# 11_power_input_and_regualtors.net
KiCad netlist of a schematic drawn in Altium Designer
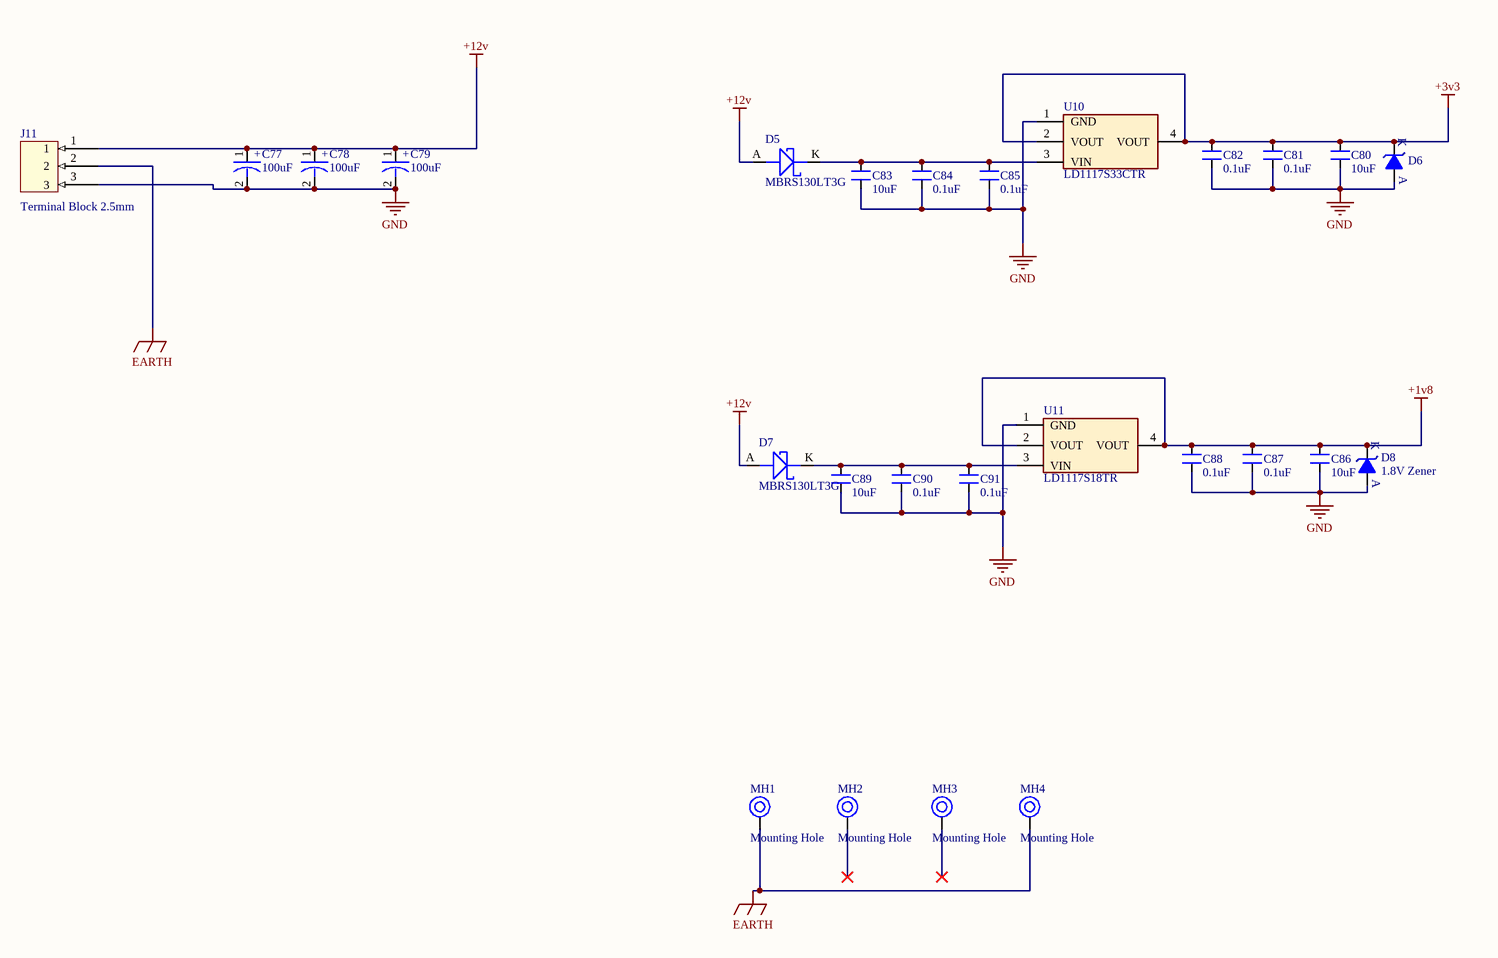
[diagram p0: [11]power_input_and_regualtors.SchDoc]

(export (version "E")
  (design (tool "Eeschema 10.0.6"))
  (components
    (comp (ref "C77")
      (value "100uF")
      (footprint "ACAP_P305_D393_H393_RAD")
      (description "100µF 50V Aluminum Polymer Capacitor Radial, Can - SMD 28mOhm 4000 Hrs @ 125°C")
      (fields
        (field (name "MANUFACTURER") "Nichicon")
        (field (name "MANUFACTURER PART NUMBER") "GYA1H101MCQ1GS")
      )
      (libsource (lib "ESTEEMPCBLIB") (part "CAP-P_100uF-50V-20%-RAD"))
    )
    (comp (ref "C78")
      (value "100uF")
      (footprint "ACAP_P305_D393_H393_RAD")
      (description "100µF 50V Aluminum Polymer Capacitor Radial, Can - SMD 28mOhm 4000 Hrs @ 125°C")
      (fields
        (field (name "MANUFACTURER") "Nichicon")
        (field (name "MANUFACTURER PART NUMBER") "GYA1H101MCQ1GS")
      )
      (libsource (lib "ESTEEMPCBLIB") (part "CAP-P_100uF-50V-20%-RAD"))
    )
    (comp (ref "C79")
      (value "100uF")
      (footprint "ACAP_P305_D393_H393_RAD")
      (description "100µF 50V Aluminum Polymer Capacitor Radial, Can - SMD 28mOhm 4000 Hrs @ 125°C")
      (fields
        (field (name "MANUFACTURER") "Nichicon")
        (field (name "MANUFACTURER PART NUMBER") "GYA1H101MCQ1GS")
      )
      (libsource (lib "ESTEEMPCBLIB") (part "CAP-P_100uF-50V-20%-RAD"))
    )
    (comp (ref "C80")
      (value "10uF")
      (footprint "CAP_1206")
      (description "10µF ±10% 50V Ceramic Capacitor X7R 1206 (3216 Metric)")
      (fields
        (field (name "MANUFACTURER") "KEMET")
        (field (name "MANUFACTURER PART NUMBER") "CL31B106KBHNNNE")
      )
      (libsource (lib "ESTEEMPCBLIB") (part "CAP_10uF-50V-10%-1206"))
    )
    (comp (ref "C81")
      (value "0.1uF")
      (footprint "CAP_0805")
      (description "0.1µF ±5% 50V Ceramic Capacitor X7R 0805 (2012 Metric)")
      (fields
        (field (name "MANUFACTURER") "AVX Corporation")
        (field (name "MANUFACTURER PART NUMBER") "08055C104JAT4A")
      )
      (libsource (lib "ESTEEMPCBLIB") (part "CAP_0.1uF-50V-5%-0805"))
    )
    (comp (ref "C82")
      (value "0.1uF")
      (footprint "CAP_0805")
      (description "0.1µF ±5% 50V Ceramic Capacitor X7R 0805 (2012 Metric)")
      (fields
        (field (name "MANUFACTURER") "AVX Corporation")
        (field (name "MANUFACTURER PART NUMBER") "08055C104JAT4A")
      )
      (libsource (lib "ESTEEMPCBLIB") (part "CAP_0.1uF-50V-5%-0805"))
    )
    (comp (ref "C83")
      (value "10uF")
      (footprint "CAP_1206")
      (description "10µF ±10% 50V Ceramic Capacitor X7R 1206 (3216 Metric)")
      (fields
        (field (name "MANUFACTURER") "KEMET")
        (field (name "MANUFACTURER PART NUMBER") "CL31B106KBHNNNE")
      )
      (libsource (lib "ESTEEMPCBLIB") (part "CAP_10uF-50V-10%-1206"))
    )
    (comp (ref "C84")
      (value "0.1uF")
      (footprint "CAP_0805")
      (description "0.1µF ±5% 50V Ceramic Capacitor X7R 0805 (2012 Metric)")
      (fields
        (field (name "MANUFACTURER") "AVX Corporation")
        (field (name "MANUFACTURER PART NUMBER") "08055C104JAT4A")
      )
      (libsource (lib "ESTEEMPCBLIB") (part "CAP_0.1uF-50V-5%-0805"))
    )
    (comp (ref "C85")
      (value "0.1uF")
      (footprint "CAP_0805")
      (description "0.1µF ±5% 50V Ceramic Capacitor X7R 0805 (2012 Metric)")
      (fields
        (field (name "MANUFACTURER") "AVX Corporation")
        (field (name "MANUFACTURER PART NUMBER") "08055C104JAT4A")
      )
      (libsource (lib "ESTEEMPCBLIB") (part "CAP_0.1uF-50V-5%-0805"))
    )
    (comp (ref "C86")
      (value "10uF")
      (footprint "CAP_1206")
      (description "10µF ±10% 50V Ceramic Capacitor X7R 1206 (3216 Metric)")
      (fields
        (field (name "MANUFACTURER") "KEMET")
        (field (name "MANUFACTURER PART NUMBER") "CL31B106KBHNNNE")
      )
      (libsource (lib "ESTEEMPCBLIB") (part "CAP_10uF-50V-10%-1206"))
    )
    (comp (ref "C87")
      (value "0.1uF")
      (footprint "CAP_0805")
      (description "0.1µF ±5% 50V Ceramic Capacitor X7R 0805 (2012 Metric)")
      (fields
        (field (name "MANUFACTURER") "AVX Corporation")
        (field (name "MANUFACTURER PART NUMBER") "08055C104JAT4A")
      )
      (libsource (lib "ESTEEMPCBLIB") (part "CAP_0.1uF-50V-5%-0805"))
    )
    (comp (ref "C88")
      (value "0.1uF")
      (footprint "CAP_0805")
      (description "0.1µF ±5% 50V Ceramic Capacitor X7R 0805 (2012 Metric)")
      (fields
        (field (name "MANUFACTURER") "AVX Corporation")
        (field (name "MANUFACTURER PART NUMBER") "08055C104JAT4A")
      )
      (libsource (lib "ESTEEMPCBLIB") (part "CAP_0.1uF-50V-5%-0805"))
    )
    (comp (ref "C89")
      (value "10uF")
      (footprint "CAP_1206")
      (description "10µF ±10% 50V Ceramic Capacitor X7R 1206 (3216 Metric)")
      (fields
        (field (name "MANUFACTURER") "KEMET")
        (field (name "MANUFACTURER PART NUMBER") "CL31B106KBHNNNE")
      )
      (libsource (lib "ESTEEMPCBLIB") (part "CAP_10uF-50V-10%-1206"))
    )
    (comp (ref "C90")
      (value "0.1uF")
      (footprint "CAP_0805")
      (description "0.1µF ±5% 50V Ceramic Capacitor X7R 0805 (2012 Metric)")
      (fields
        (field (name "MANUFACTURER") "AVX Corporation")
        (field (name "MANUFACTURER PART NUMBER") "08055C104JAT4A")
      )
      (libsource (lib "ESTEEMPCBLIB") (part "CAP_0.1uF-50V-5%-0805"))
    )
    (comp (ref "C91")
      (value "0.1uF")
      (footprint "CAP_0805")
      (description "0.1µF ±5% 50V Ceramic Capacitor X7R 0805 (2012 Metric)")
      (fields
        (field (name "MANUFACTURER") "AVX Corporation")
        (field (name "MANUFACTURER PART NUMBER") "08055C104JAT4A")
      )
      (libsource (lib "ESTEEMPCBLIB") (part "CAP_0.1uF-50V-5%-0805"))
    )
    (comp (ref "D5")
      (value "MBRS130LT3G")
      (footprint "DIO_SMB_DO-214AA")
      (description "Diode Schottky 30V 2A Surface Mount SMB")
      (fields (field (name "MANUFACTURER") "ON Semiconductor"))
      (libsource (lib "ESTEEMPCBLIB") (part "DIO-S_445mV-30V-2A-SMB"))
    )
    (comp (ref "D6")
      (value "BZT52C3V3-7-F")
      (footprint "DIO_SOD-123")
      (description "Zener Diode 3.3V 500mW ±6% Surface Mount SOD-123")
      (fields (field (name "MANUFACTURER") "Diodes Incorporated"))
      (libsource (lib "ESTEEMPCBLIB") (part "DIO-Z_3.3V-500mW-SOD123"))
    )
    (comp (ref "D7")
      (value "MBRS130LT3G")
      (footprint "DIO_SMB_DO-214AA")
      (description "Diode Schottky 30V 2A Surface Mount SMB")
      (fields (field (name "MANUFACTURER") "ON Semiconductor"))
      (libsource (lib "ESTEEMPCBLIB") (part "DIO-S_445mV-30V-2A-SMB"))
    )
    (comp (ref "D8")
      (value "1.8V Zener")
      (footprint "DIO_DO-213AB_SMD")
      (description "Zener Diode 1.8V 500mW ±5% Surface Mount DO-213AA")
      (libsource (lib "ESTEEMPCBLIB") (part "DIO-Z_1.8V-500mW-DO213AA"))
    )
    (comp (ref "J11")
      (value "Terminal Block 2.5mm")
      (footprint "CON3_100_TB_TH_ST")
      (description "3 Pins, 1 Row 2.54mm Pitch, straight Connector, male")
      (fields
        (field (name "MANUFACTURER PART NUMBER") "1725669")
        (field (name "MANUFACTURER") "Phoenix Contact")
      )
      (libsource (lib "ESTEEMPCBLIB") (part "CON-TB_3X1-100-ST-TH"))
    )
    (comp (ref "MH1")
      (value "Mounting Hole")
      (footprint "MOUNTING")
      (fields (field (name "MANUFACTURER PART NUMBER") "NA"))
      (libsource (lib "ESTEEMPCBLIB") (part "MH_3.5H_6D"))
    )
    (comp (ref "MH2")
      (value "Mounting Hole")
      (footprint "MOUNTING")
      (fields (field (name "MANUFACTURER PART NUMBER") "NA"))
      (libsource (lib "ESTEEMPCBLIB") (part "MH_3.5H_6D"))
    )
    (comp (ref "MH3")
      (value "Mounting Hole")
      (footprint "MOUNTING")
      (fields (field (name "MANUFACTURER PART NUMBER") "NA"))
      (libsource (lib "ESTEEMPCBLIB") (part "MH_3.5H_6D"))
    )
    (comp (ref "MH4")
      (value "Mounting Hole")
      (footprint "MOUNTING")
      (fields (field (name "MANUFACTURER PART NUMBER") "NA"))
      (libsource (lib "ESTEEMPCBLIB") (part "MH_3.5H_6D"))
    )
    (comp (ref "U10")
      (value "LD1117S33CTR")
      (footprint "SOT223_3")
      (description "Linear Voltage Regulator IC 1 Output 800mA SOT-223")
      (fields (field (name "MANUFACTURER") "STMicroelectronics"))
      (libsource (lib "ESTEEMPCBLIB") (part "REG_15V-3.3V-0.9A-12W-SOT223"))
    )
    (comp (ref "U11")
      (value "LD1117S18TR")
      (footprint "SOT223_3")
      (description "LDO Voltage Regulators 1.8V 0.8A Positive")
      (fields (field (name "MANUFACTURER") "STMicroelectronics"))
      (libsource (lib "ESTEEMPCBLIB") (part "REG_15V-1.8V-0.8A-1.4W-SOT223"))
    )
  )
  (nets
    (net (code "1") (name "+1v8") (class "Default")
      (node (ref "C86") (pin "2") (pinfunction "2_2") (pintype "passive"))
      (node (ref "C87") (pin "2") (pinfunction "2_2") (pintype "passive"))
      (node (ref "C88") (pin "2") (pinfunction "2_2") (pintype "passive"))
      (node (ref "D8") (pin "K") (pinfunction "K_K") (pintype "passive"))
      (node (ref "U11") (pin "2") (pinfunction "VOUT_2") (pintype "passive"))
      (node (ref "U11") (pin "4") (pinfunction "VOUT_4") (pintype "passive"))
    )
    (net (code "2") (name "+3v3") (class "Default")
      (node (ref "C80") (pin "2") (pinfunction "2_2") (pintype "passive"))
      (node (ref "C81") (pin "2") (pinfunction "2_2") (pintype "passive"))
      (node (ref "C82") (pin "2") (pinfunction "2_2") (pintype "passive"))
      (node (ref "D6") (pin "K") (pinfunction "K_K") (pintype "passive"))
      (node (ref "U10") (pin "2") (pinfunction "VOUT_2") (pintype "passive"))
      (node (ref "U10") (pin "4") (pinfunction "VOUT_4") (pintype "passive"))
    )
    (net (code "3") (name "+12v") (class "Default")
      (node (ref "C77") (pin "1") (pinfunction "1_1") (pintype "passive"))
      (node (ref "C78") (pin "1") (pinfunction "1_1") (pintype "passive"))
      (node (ref "C79") (pin "1") (pinfunction "1_1") (pintype "passive"))
      (node (ref "D5") (pin "A") (pinfunction "A_A") (pintype "passive"))
      (node (ref "D7") (pin "A") (pinfunction "A_A") (pintype "passive"))
      (node (ref "J11") (pin "1") (pinfunction "1_1") (pintype "input"))
    )
    (net (code "4") (name "EARTH") (class "Default")
      (node (ref "J11") (pin "2") (pinfunction "2_2") (pintype "input"))
      (node (ref "MH1") (pin "1") (pinfunction "1_1") (pintype "passive"))
      (node (ref "MH4") (pin "1") (pinfunction "1_1") (pintype "passive"))
    )
    (net (code "5") (name "GND") (class "Default")
      (node (ref "C77") (pin "2") (pinfunction "2_2") (pintype "passive"))
      (node (ref "C78") (pin "2") (pinfunction "2_2") (pintype "passive"))
      (node (ref "C79") (pin "2") (pinfunction "2_2") (pintype "passive"))
      (node (ref "C80") (pin "1") (pinfunction "1_1") (pintype "passive"))
      (node (ref "C81") (pin "1") (pinfunction "1_1") (pintype "passive"))
      (node (ref "C82") (pin "1") (pinfunction "1_1") (pintype "passive"))
      (node (ref "C83") (pin "1") (pinfunction "1_1") (pintype "passive"))
      (node (ref "C84") (pin "1") (pinfunction "1_1") (pintype "passive"))
      (node (ref "C85") (pin "1") (pinfunction "1_1") (pintype "passive"))
      (node (ref "C86") (pin "1") (pinfunction "1_1") (pintype "passive"))
      (node (ref "C87") (pin "1") (pinfunction "1_1") (pintype "passive"))
      (node (ref "C88") (pin "1") (pinfunction "1_1") (pintype "passive"))
      (node (ref "C89") (pin "1") (pinfunction "1_1") (pintype "passive"))
      (node (ref "C90") (pin "1") (pinfunction "1_1") (pintype "passive"))
      (node (ref "C91") (pin "1") (pinfunction "1_1") (pintype "passive"))
      (node (ref "D6") (pin "A") (pinfunction "A_A") (pintype "passive"))
      (node (ref "D8") (pin "A") (pinfunction "A_A") (pintype "passive"))
      (node (ref "J11") (pin "3") (pinfunction "3_3") (pintype "input"))
      (node (ref "U10") (pin "1") (pinfunction "GND_1") (pintype "passive"))
      (node (ref "U11") (pin "1") (pinfunction "GND_1") (pintype "passive"))
    )
    (net (code "6") (name "Net-(U10-VIN)") (class "Default")
      (node (ref "C83") (pin "2") (pinfunction "2_2") (pintype "passive"))
      (node (ref "C84") (pin "2") (pinfunction "2_2") (pintype "passive"))
      (node (ref "C85") (pin "2") (pinfunction "2_2") (pintype "passive"))
      (node (ref "D5") (pin "K") (pinfunction "K_K") (pintype "passive"))
      (node (ref "U10") (pin "3") (pinfunction "VIN_3") (pintype "passive"))
    )
    (net (code "7") (name "Net-(U11-VIN)") (class "Default")
      (node (ref "C89") (pin "2") (pinfunction "2_2") (pintype "passive"))
      (node (ref "C90") (pin "2") (pinfunction "2_2") (pintype "passive"))
      (node (ref "C91") (pin "2") (pinfunction "2_2") (pintype "passive"))
      (node (ref "D7") (pin "K") (pinfunction "K_K") (pintype "passive"))
      (node (ref "U11") (pin "3") (pinfunction "VIN_3") (pintype "passive"))
    )
    (net (code "8") (name "unconnected-(MH2-Pad1)") (class "Default")
      (node (ref "MH2") (pin "1") (pinfunction "1_1") (pintype "passive+no_connect"))
    )
    (net (code "9") (name "unconnected-(MH3-Pad1)") (class "Default")
      (node (ref "MH3") (pin "1") (pinfunction "1_1") (pintype "passive+no_connect"))
    )
  )
)
